# base.net
KiCad netlist of a schematic drawn in EAGLE
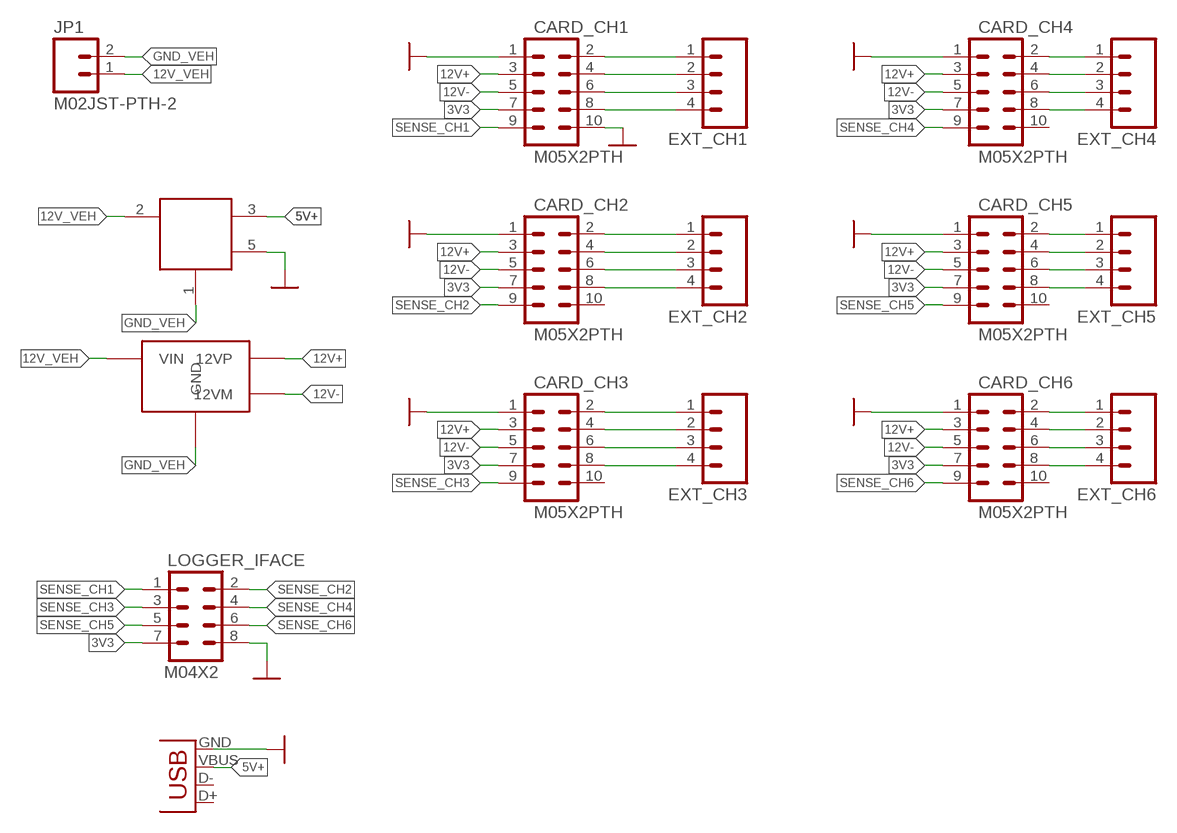
[diagram p0: schematic, sheet 1]

(export (version "E")
  (design (tool "Eeschema 10.0.6"))
  (components
    (comp (ref "CARD_CH1")
      (value "M05X2PTH")
      (footprint "eagle-import:AVR_ICSP")
      (libsource (lib "eagle-import") (part "M05X2PTH"))
    )
    (comp (ref "CARD_CH2")
      (value "M05X2PTH")
      (footprint "eagle-import:AVR_ICSP")
      (libsource (lib "eagle-import") (part "M05X2PTH"))
    )
    (comp (ref "CARD_CH3")
      (value "M05X2PTH")
      (footprint "eagle-import:AVR_ICSP")
      (libsource (lib "eagle-import") (part "M05X2PTH"))
    )
    (comp (ref "CARD_CH4")
      (value "M05X2PTH")
      (footprint "eagle-import:AVR_ICSP")
      (libsource (lib "eagle-import") (part "M05X2PTH"))
    )
    (comp (ref "CARD_CH5")
      (value "M05X2PTH")
      (footprint "eagle-import:AVR_ICSP")
      (libsource (lib "eagle-import") (part "M05X2PTH"))
    )
    (comp (ref "CARD_CH6")
      (value "M05X2PTH")
      (footprint "eagle-import:AVR_ICSP")
      (libsource (lib "eagle-import") (part "M05X2PTH"))
    )
    (comp (ref "EXT_CH1")
      (value "M04PTH")
      (footprint "eagle-import:1X04")
      (libsource (lib "eagle-import") (part "M04PTH"))
    )
    (comp (ref "EXT_CH2")
      (value "M04PTH")
      (footprint "eagle-import:1X04")
      (libsource (lib "eagle-import") (part "M04PTH"))
    )
    (comp (ref "EXT_CH3")
      (value "M04PTH")
      (footprint "eagle-import:1X04")
      (libsource (lib "eagle-import") (part "M04PTH"))
    )
    (comp (ref "EXT_CH4")
      (value "M04PTH")
      (footprint "eagle-import:1X04")
      (libsource (lib "eagle-import") (part "M04PTH"))
    )
    (comp (ref "EXT_CH5")
      (value "M04PTH")
      (footprint "eagle-import:1X04")
      (libsource (lib "eagle-import") (part "M04PTH"))
    )
    (comp (ref "EXT_CH6")
      (value "M04PTH")
      (footprint "eagle-import:1X04")
      (libsource (lib "eagle-import") (part "M04PTH"))
    )
    (comp (ref "JP1")
      (value "M02JST-PTH-2")
      (footprint "eagle-import:JST-2-PTH")
      (libsource (lib "eagle-import") (part "M02JST-PTH-2"))
    )
    (comp (ref "JP2")
      (value "USB-A-S")
      (footprint "eagle-import:USB-A-S")
      (libsource (lib "eagle-import") (part "USB-A-S"))
    )
    (comp (ref "LOGGER_IFACE")
      (value "M04X2")
      (footprint "eagle-import:2X4")
      (libsource (lib "eagle-import") (part "M04X2"))
    )
    (comp (ref "U$1")
      (value "NMXS1205UC_PTH")
      (footprint "eagle-import:NMXS1205UC_PTH")
      (libsource (lib "eagle-import") (part "NMXS1205UC_PTH"))
    )
    (comp (ref "U$2")
      (value "TMR3122_12_CONV_PTH")
      (footprint "eagle-import:TMR3122_12_CONV_PTH")
      (libsource (lib "eagle-import") (part "TMR3122_12_CONV_PTH"))
    )
  )
  (nets
    (net (code "1") (name "3V3") (class "Default")
      (node (ref "CARD_CH1") (pin "7") (pinfunction "7_7") (pintype "passive"))
      (node (ref "CARD_CH2") (pin "7") (pinfunction "7_7") (pintype "passive"))
      (node (ref "CARD_CH3") (pin "7") (pinfunction "7_7") (pintype "passive"))
      (node (ref "CARD_CH4") (pin "7") (pinfunction "7_7") (pintype "passive"))
      (node (ref "CARD_CH5") (pin "7") (pinfunction "7_7") (pintype "passive"))
      (node (ref "CARD_CH6") (pin "7") (pinfunction "7_7") (pintype "passive"))
      (node (ref "LOGGER_IFACE") (pin "7") (pinfunction "7_7") (pintype "passive"))
    )
    (net (code "2") (name "5V+") (class "Default")
      (node (ref "JP2") (pin "VBUS") (pinfunction "VBUS_VBUS") (pintype "bidirectional"))
      (node (ref "U$1") (pin "3") (pinfunction "5VOUT_3") (pintype "bidirectional"))
    )
    (net (code "3") (name "12V+") (class "Default")
      (node (ref "CARD_CH1") (pin "3") (pinfunction "3_3") (pintype "passive"))
      (node (ref "CARD_CH2") (pin "3") (pinfunction "3_3") (pintype "passive"))
      (node (ref "CARD_CH3") (pin "3") (pinfunction "3_3") (pintype "passive"))
      (node (ref "CARD_CH4") (pin "3") (pinfunction "3_3") (pintype "passive"))
      (node (ref "CARD_CH5") (pin "3") (pinfunction "3_3") (pintype "passive"))
      (node (ref "CARD_CH6") (pin "3") (pinfunction "3_3") (pintype "passive"))
      (node (ref "U$2") (pin "5") (pinfunction "12VP_5") (pintype "bidirectional"))
    )
    (net (code "4") (name "12V-") (class "Default")
      (node (ref "CARD_CH1") (pin "5") (pinfunction "5_5") (pintype "passive"))
      (node (ref "CARD_CH2") (pin "5") (pinfunction "5_5") (pintype "passive"))
      (node (ref "CARD_CH3") (pin "5") (pinfunction "5_5") (pintype "passive"))
      (node (ref "CARD_CH4") (pin "5") (pinfunction "5_5") (pintype "passive"))
      (node (ref "CARD_CH5") (pin "5") (pinfunction "5_5") (pintype "passive"))
      (node (ref "CARD_CH6") (pin "5") (pinfunction "5_5") (pintype "passive"))
      (node (ref "U$2") (pin "6") (pinfunction "12VM_6") (pintype "bidirectional"))
    )
    (net (code "5") (name "12V_VEH") (class "Default")
      (node (ref "JP1") (pin "1") (pinfunction "1_1") (pintype "passive"))
      (node (ref "U$1") (pin "2") (pinfunction "VIN_2") (pintype "bidirectional"))
      (node (ref "U$2") (pin "2") (pinfunction "VIN_2") (pintype "bidirectional"))
    )
    (net (code "6") (name "GND") (class "Default")
      (node (ref "CARD_CH1") (pin "1") (pinfunction "1_1") (pintype "passive"))
      (node (ref "CARD_CH1") (pin "10") (pinfunction "10_10") (pintype "passive"))
      (node (ref "CARD_CH2") (pin "1") (pinfunction "1_1") (pintype "passive"))
      (node (ref "CARD_CH3") (pin "1") (pinfunction "1_1") (pintype "passive"))
      (node (ref "CARD_CH4") (pin "1") (pinfunction "1_1") (pintype "passive"))
      (node (ref "CARD_CH5") (pin "1") (pinfunction "1_1") (pintype "passive"))
      (node (ref "CARD_CH6") (pin "1") (pinfunction "1_1") (pintype "passive"))
      (node (ref "JP2") (pin "GND") (pinfunction "GND_GND") (pintype "bidirectional"))
      (node (ref "LOGGER_IFACE") (pin "8") (pinfunction "8_8") (pintype "passive"))
      (node (ref "U$1") (pin "5") (pinfunction "GNDOUT_5") (pintype "bidirectional"))
    )
    (net (code "7") (name "GND_VEH") (class "Default")
      (node (ref "JP1") (pin "2") (pinfunction "2_2") (pintype "passive"))
      (node (ref "U$1") (pin "1") (pinfunction "GND_1") (pintype "bidirectional"))
      (node (ref "U$2") (pin "1") (pinfunction "GND_1") (pintype "bidirectional"))
    )
    (net (code "8") (name "Net-(CARD_CH1-Pad2)") (class "Default")
      (node (ref "CARD_CH1") (pin "2") (pinfunction "2_2") (pintype "passive"))
      (node (ref "EXT_CH1") (pin "1") (pinfunction "1_1") (pintype "passive"))
    )
    (net (code "9") (name "Net-(CARD_CH1-Pad4)") (class "Default")
      (node (ref "CARD_CH1") (pin "4") (pinfunction "4_4") (pintype "passive"))
      (node (ref "EXT_CH1") (pin "2") (pinfunction "2_2") (pintype "passive"))
    )
    (net (code "10") (name "Net-(CARD_CH1-Pad6)") (class "Default")
      (node (ref "CARD_CH1") (pin "6") (pinfunction "6_6") (pintype "passive"))
      (node (ref "EXT_CH1") (pin "3") (pinfunction "3_3") (pintype "passive"))
    )
    (net (code "11") (name "Net-(CARD_CH1-Pad8)") (class "Default")
      (node (ref "CARD_CH1") (pin "8") (pinfunction "8_8") (pintype "passive"))
      (node (ref "EXT_CH1") (pin "4") (pinfunction "4_4") (pintype "passive"))
    )
    (net (code "12") (name "Net-(CARD_CH2-Pad2)") (class "Default")
      (node (ref "CARD_CH2") (pin "2") (pinfunction "2_2") (pintype "passive"))
      (node (ref "EXT_CH2") (pin "1") (pinfunction "1_1") (pintype "passive"))
    )
    (net (code "13") (name "Net-(CARD_CH2-Pad4)") (class "Default")
      (node (ref "CARD_CH2") (pin "4") (pinfunction "4_4") (pintype "passive"))
      (node (ref "EXT_CH2") (pin "2") (pinfunction "2_2") (pintype "passive"))
    )
    (net (code "14") (name "Net-(CARD_CH2-Pad6)") (class "Default")
      (node (ref "CARD_CH2") (pin "6") (pinfunction "6_6") (pintype "passive"))
      (node (ref "EXT_CH2") (pin "3") (pinfunction "3_3") (pintype "passive"))
    )
    (net (code "15") (name "Net-(CARD_CH2-Pad8)") (class "Default")
      (node (ref "CARD_CH2") (pin "8") (pinfunction "8_8") (pintype "passive"))
      (node (ref "EXT_CH2") (pin "4") (pinfunction "4_4") (pintype "passive"))
    )
    (net (code "16") (name "Net-(CARD_CH3-Pad2)") (class "Default")
      (node (ref "CARD_CH3") (pin "2") (pinfunction "2_2") (pintype "passive"))
      (node (ref "EXT_CH3") (pin "1") (pinfunction "1_1") (pintype "passive"))
    )
    (net (code "17") (name "Net-(CARD_CH3-Pad4)") (class "Default")
      (node (ref "CARD_CH3") (pin "4") (pinfunction "4_4") (pintype "passive"))
      (node (ref "EXT_CH3") (pin "2") (pinfunction "2_2") (pintype "passive"))
    )
    (net (code "18") (name "Net-(CARD_CH3-Pad6)") (class "Default")
      (node (ref "CARD_CH3") (pin "6") (pinfunction "6_6") (pintype "passive"))
      (node (ref "EXT_CH3") (pin "3") (pinfunction "3_3") (pintype "passive"))
    )
    (net (code "19") (name "Net-(CARD_CH3-Pad8)") (class "Default")
      (node (ref "CARD_CH3") (pin "8") (pinfunction "8_8") (pintype "passive"))
      (node (ref "EXT_CH3") (pin "4") (pinfunction "4_4") (pintype "passive"))
    )
    (net (code "20") (name "Net-(CARD_CH4-Pad2)") (class "Default")
      (node (ref "CARD_CH4") (pin "2") (pinfunction "2_2") (pintype "passive"))
      (node (ref "EXT_CH4") (pin "1") (pinfunction "1_1") (pintype "passive"))
    )
    (net (code "21") (name "Net-(CARD_CH4-Pad4)") (class "Default")
      (node (ref "CARD_CH4") (pin "4") (pinfunction "4_4") (pintype "passive"))
      (node (ref "EXT_CH4") (pin "2") (pinfunction "2_2") (pintype "passive"))
    )
    (net (code "22") (name "Net-(CARD_CH4-Pad6)") (class "Default")
      (node (ref "CARD_CH4") (pin "6") (pinfunction "6_6") (pintype "passive"))
      (node (ref "EXT_CH4") (pin "3") (pinfunction "3_3") (pintype "passive"))
    )
    (net (code "23") (name "Net-(CARD_CH4-Pad8)") (class "Default")
      (node (ref "CARD_CH4") (pin "8") (pinfunction "8_8") (pintype "passive"))
      (node (ref "EXT_CH4") (pin "4") (pinfunction "4_4") (pintype "passive"))
    )
    (net (code "24") (name "Net-(CARD_CH5-Pad2)") (class "Default")
      (node (ref "CARD_CH5") (pin "2") (pinfunction "2_2") (pintype "passive"))
      (node (ref "EXT_CH5") (pin "1") (pinfunction "1_1") (pintype "passive"))
    )
    (net (code "25") (name "Net-(CARD_CH5-Pad4)") (class "Default")
      (node (ref "CARD_CH5") (pin "4") (pinfunction "4_4") (pintype "passive"))
      (node (ref "EXT_CH5") (pin "2") (pinfunction "2_2") (pintype "passive"))
    )
    (net (code "26") (name "Net-(CARD_CH5-Pad6)") (class "Default")
      (node (ref "CARD_CH5") (pin "6") (pinfunction "6_6") (pintype "passive"))
      (node (ref "EXT_CH5") (pin "3") (pinfunction "3_3") (pintype "passive"))
    )
    (net (code "27") (name "Net-(CARD_CH5-Pad8)") (class "Default")
      (node (ref "CARD_CH5") (pin "8") (pinfunction "8_8") (pintype "passive"))
      (node (ref "EXT_CH5") (pin "4") (pinfunction "4_4") (pintype "passive"))
    )
    (net (code "28") (name "Net-(CARD_CH6-Pad2)") (class "Default")
      (node (ref "CARD_CH6") (pin "2") (pinfunction "2_2") (pintype "passive"))
      (node (ref "EXT_CH6") (pin "1") (pinfunction "1_1") (pintype "passive"))
    )
    (net (code "29") (name "Net-(CARD_CH6-Pad4)") (class "Default")
      (node (ref "CARD_CH6") (pin "4") (pinfunction "4_4") (pintype "passive"))
      (node (ref "EXT_CH6") (pin "2") (pinfunction "2_2") (pintype "passive"))
    )
    (net (code "30") (name "Net-(CARD_CH6-Pad6)") (class "Default")
      (node (ref "CARD_CH6") (pin "6") (pinfunction "6_6") (pintype "passive"))
      (node (ref "EXT_CH6") (pin "3") (pinfunction "3_3") (pintype "passive"))
    )
    (net (code "31") (name "Net-(CARD_CH6-Pad8)") (class "Default")
      (node (ref "CARD_CH6") (pin "8") (pinfunction "8_8") (pintype "passive"))
      (node (ref "EXT_CH6") (pin "4") (pinfunction "4_4") (pintype "passive"))
    )
    (net (code "32") (name "SENSE_CH1") (class "Default")
      (node (ref "CARD_CH1") (pin "9") (pinfunction "9_9") (pintype "passive"))
      (node (ref "LOGGER_IFACE") (pin "1") (pinfunction "1_1") (pintype "passive"))
    )
    (net (code "33") (name "SENSE_CH2") (class "Default")
      (node (ref "CARD_CH2") (pin "9") (pinfunction "9_9") (pintype "passive"))
      (node (ref "LOGGER_IFACE") (pin "2") (pinfunction "2_2") (pintype "passive"))
    )
    (net (code "34") (name "SENSE_CH3") (class "Default")
      (node (ref "CARD_CH3") (pin "9") (pinfunction "9_9") (pintype "passive"))
      (node (ref "LOGGER_IFACE") (pin "3") (pinfunction "3_3") (pintype "passive"))
    )
    (net (code "35") (name "SENSE_CH4") (class "Default")
      (node (ref "CARD_CH4") (pin "9") (pinfunction "9_9") (pintype "passive"))
      (node (ref "LOGGER_IFACE") (pin "4") (pinfunction "4_4") (pintype "passive"))
    )
    (net (code "36") (name "SENSE_CH5") (class "Default")
      (node (ref "CARD_CH5") (pin "9") (pinfunction "9_9") (pintype "passive"))
      (node (ref "LOGGER_IFACE") (pin "5") (pinfunction "5_5") (pintype "passive"))
    )
    (net (code "37") (name "SENSE_CH6") (class "Default")
      (node (ref "CARD_CH6") (pin "9") (pinfunction "9_9") (pintype "passive"))
      (node (ref "LOGGER_IFACE") (pin "6") (pinfunction "6_6") (pintype "passive"))
    )
    (net (code "38") (name "unconnected-(CARD_CH2-Pad10)") (class "Default")
      (node (ref "CARD_CH2") (pin "10") (pinfunction "10_10") (pintype "passive"))
    )
    (net (code "39") (name "unconnected-(CARD_CH3-Pad10)") (class "Default")
      (node (ref "CARD_CH3") (pin "10") (pinfunction "10_10") (pintype "passive"))
    )
    (net (code "40") (name "unconnected-(CARD_CH4-Pad10)") (class "Default")
      (node (ref "CARD_CH4") (pin "10") (pinfunction "10_10") (pintype "passive"))
    )
    (net (code "41") (name "unconnected-(CARD_CH5-Pad10)") (class "Default")
      (node (ref "CARD_CH5") (pin "10") (pinfunction "10_10") (pintype "passive"))
    )
    (net (code "42") (name "unconnected-(CARD_CH6-Pad10)") (class "Default")
      (node (ref "CARD_CH6") (pin "10") (pinfunction "10_10") (pintype "passive"))
    )
    (net (code "43") (name "unconnected-(JP2-PadD+)") (class "Default")
      (node (ref "JP2") (pin "D+") (pinfunction "D+_D+") (pintype "bidirectional"))
    )
    (net (code "44") (name "unconnected-(JP2-PadD-)") (class "Default")
      (node (ref "JP2") (pin "D-") (pinfunction "D-_D-") (pintype "bidirectional"))
    )
  )
)
